# Sheet1.net
KiCad netlist of a schematic drawn in Altium Designer
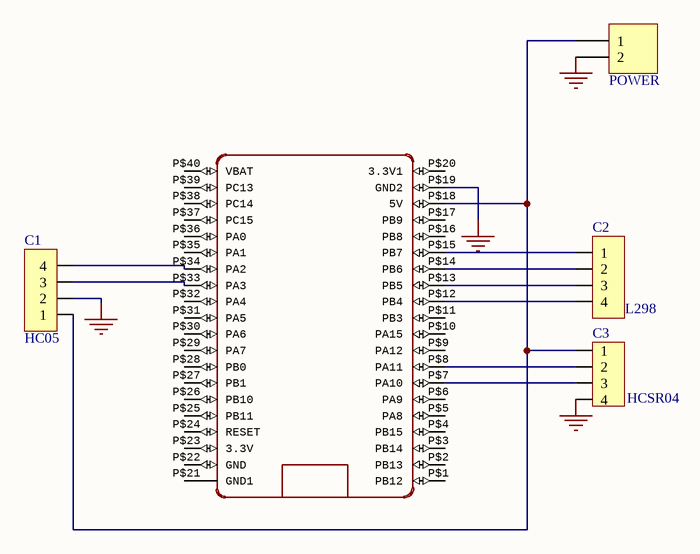
[diagram p0: Sheet1.SchDoc]

(export (version "E")
  (design (tool "Eeschema 10.0.6"))
  (components
    (comp (ref "C1")
      (value "HC05")
      (footprint "JP4-C1T")
      (description "WR-PHD 2.54 mm Angled Socket Header")
      (fields
        (field (name "MANUFACTURER") "Würth Elektronik eiSos GmbH")
        (field (name "PARTNO") "613004143121")
        (field (name "CREATED BY") "Karrer Zheng")
      )
      (libsource (lib "") (part "JP4_1"))
    )
    (comp (ref "C2")
      (value "L298")
      (footprint "JP4-C1T")
      (description "WR-PHD 2.54 mm Angled Socket Header")
      (fields
        (field (name "MANUFACTURER") "Würth Elektronik eiSos GmbH")
        (field (name "PARTNO") "613004143121")
        (field (name "CREATED BY") "Karrer Zheng")
      )
      (libsource (lib "LIBRARYALT") (part "JP4"))
    )
    (comp (ref "C3")
      (value "HCSR04")
      (footprint "Header4")
      (description "Header IDC, 4 x 1 Pin Vertical 2.54mm Pitch (Non-Boxed, Male)")
      (fields
        (field (name "MANUFACTURER") "Würth Elektronik eiSos GmbH")
        (field (name "PARTNO") "613002143121")
        (field (name "CREATED BY") "Karrer Zheng")
      )
      (libsource (lib "LIBRARYALT") (part "Header4"))
    )
    (comp (ref "POWER")
      (value "Header 2_1")
      (footprint "HED2")
      (description "Header, 2-Pin")
      (fields (field (name "MANUFACTURER") "Generic Components"))
      (libsource (lib "echipkool-com-library") (part "Header 2_1"))
    )
    (comp (ref "U")
      (value "BLUE_PILL")
      (footprint "BLUE_PILL")
      (libsource (lib "BluePill") (part "BLUE_PILL"))
    )
  )
  (nets
    (net (code "1") (name "GND") (class "Default")
      (node (ref "C1") (pin "2") (pinfunction "2_2") (pintype "passive"))
      (node (ref "C3") (pin "4") (pinfunction "4_4") (pintype "passive"))
      (node (ref "POWER") (pin "2") (pinfunction "2_2") (pintype "passive"))
      (node (ref "U") (pin "P$19") (pinfunction "GND2_P$19") (pintype "bidirectional"))
    )
    (net (code "2") (name "Net-(U-5V)") (class "Default")
      (node (ref "C1") (pin "1") (pinfunction "1_1") (pintype "passive"))
      (node (ref "C3") (pin "1") (pinfunction "1_1") (pintype "passive"))
      (node (ref "POWER") (pin "1") (pinfunction "1_1") (pintype "passive"))
      (node (ref "U") (pin "P$18") (pinfunction "5V_P$18") (pintype "bidirectional"))
    )
    (net (code "3") (name "Net-(U-PA2)") (class "Default")
      (node (ref "C1") (pin "4") (pinfunction "4_4") (pintype "passive"))
      (node (ref "U") (pin "P$34") (pinfunction "PA2_P$34") (pintype "bidirectional"))
    )
    (net (code "4") (name "Net-(U-PA3)") (class "Default")
      (node (ref "C1") (pin "3") (pinfunction "3_3") (pintype "passive"))
      (node (ref "U") (pin "P$33") (pinfunction "PA3_P$33") (pintype "bidirectional"))
    )
    (net (code "5") (name "Net-(U-PA10)") (class "Default")
      (node (ref "C3") (pin "3") (pinfunction "3_3") (pintype "passive"))
      (node (ref "U") (pin "P$7") (pinfunction "PA10_P$7") (pintype "bidirectional"))
    )
    (net (code "6") (name "Net-(U-PA11)") (class "Default")
      (node (ref "C3") (pin "2") (pinfunction "2_2") (pintype "passive"))
      (node (ref "U") (pin "P$8") (pinfunction "PA11_P$8") (pintype "bidirectional"))
    )
    (net (code "7") (name "Net-(U-PB4)") (class "Default")
      (node (ref "C2") (pin "4") (pinfunction "4_4") (pintype "passive"))
      (node (ref "U") (pin "P$12") (pinfunction "PB4_P$12") (pintype "bidirectional"))
    )
    (net (code "8") (name "Net-(U-PB5)") (class "Default")
      (node (ref "C2") (pin "3") (pinfunction "3_3") (pintype "passive"))
      (node (ref "U") (pin "P$13") (pinfunction "PB5_P$13") (pintype "bidirectional"))
    )
    (net (code "9") (name "Net-(U-PB6)") (class "Default")
      (node (ref "C2") (pin "2") (pinfunction "2_2") (pintype "passive"))
      (node (ref "U") (pin "P$14") (pinfunction "PB6_P$14") (pintype "bidirectional"))
    )
    (net (code "10") (name "Net-(U-PB7)") (class "Default")
      (node (ref "C2") (pin "1") (pinfunction "1_1") (pintype "passive"))
      (node (ref "U") (pin "P$15") (pinfunction "PB7_P$15") (pintype "bidirectional"))
    )
    (net (code "11") (name "unconnected-(U-3.3V-PadP$23)") (class "Default")
      (node (ref "U") (pin "P$23") (pinfunction "3.3V_P$23") (pintype "bidirectional"))
    )
    (net (code "12") (name "unconnected-(U-3.3V1-PadP$20)") (class "Default")
      (node (ref "U") (pin "P$20") (pinfunction "3.3V1_P$20") (pintype "bidirectional"))
    )
    (net (code "13") (name "unconnected-(U-GND-PadP$22)") (class "Default")
      (node (ref "U") (pin "P$22") (pinfunction "GND_P$22") (pintype "bidirectional"))
    )
    (net (code "14") (name "unconnected-(U-GND1-PadP$21)") (class "Default")
      (node (ref "U") (pin "P$21") (pinfunction "GND1_P$21") (pintype "power_in"))
    )
    (net (code "15") (name "unconnected-(U-PA0-PadP$36)") (class "Default")
      (node (ref "U") (pin "P$36") (pinfunction "PA0_P$36") (pintype "bidirectional"))
    )
    (net (code "16") (name "unconnected-(U-PA1-PadP$35)") (class "Default")
      (node (ref "U") (pin "P$35") (pinfunction "PA1_P$35") (pintype "bidirectional"))
    )
    (net (code "17") (name "unconnected-(U-PA4-PadP$32)") (class "Default")
      (node (ref "U") (pin "P$32") (pinfunction "PA4_P$32") (pintype "bidirectional"))
    )
    (net (code "18") (name "unconnected-(U-PA5-PadP$31)") (class "Default")
      (node (ref "U") (pin "P$31") (pinfunction "PA5_P$31") (pintype "bidirectional"))
    )
    (net (code "19") (name "unconnected-(U-PA6-PadP$30)") (class "Default")
      (node (ref "U") (pin "P$30") (pinfunction "PA6_P$30") (pintype "bidirectional"))
    )
    (net (code "20") (name "unconnected-(U-PA7-PadP$29)") (class "Default")
      (node (ref "U") (pin "P$29") (pinfunction "PA7_P$29") (pintype "bidirectional"))
    )
    (net (code "21") (name "unconnected-(U-PA8-PadP$5)") (class "Default")
      (node (ref "U") (pin "P$5") (pinfunction "PA8_P$5") (pintype "bidirectional"))
    )
    (net (code "22") (name "unconnected-(U-PA9-PadP$6)") (class "Default")
      (node (ref "U") (pin "P$6") (pinfunction "PA9_P$6") (pintype "bidirectional"))
    )
    (net (code "23") (name "unconnected-(U-PA12-PadP$9)") (class "Default")
      (node (ref "U") (pin "P$9") (pinfunction "PA12_P$9") (pintype "bidirectional"))
    )
    (net (code "24") (name "unconnected-(U-PA15-PadP$10)") (class "Default")
      (node (ref "U") (pin "P$10") (pinfunction "PA15_P$10") (pintype "bidirectional"))
    )
    (net (code "25") (name "unconnected-(U-PB0-PadP$28)") (class "Default")
      (node (ref "U") (pin "P$28") (pinfunction "PB0_P$28") (pintype "bidirectional"))
    )
    (net (code "26") (name "unconnected-(U-PB1-PadP$27)") (class "Default")
      (node (ref "U") (pin "P$27") (pinfunction "PB1_P$27") (pintype "bidirectional"))
    )
    (net (code "27") (name "unconnected-(U-PB3-PadP$11)") (class "Default")
      (node (ref "U") (pin "P$11") (pinfunction "PB3_P$11") (pintype "bidirectional"))
    )
    (net (code "28") (name "unconnected-(U-PB8-PadP$16)") (class "Default")
      (node (ref "U") (pin "P$16") (pinfunction "PB8_P$16") (pintype "bidirectional"))
    )
    (net (code "29") (name "unconnected-(U-PB9-PadP$17)") (class "Default")
      (node (ref "U") (pin "P$17") (pinfunction "PB9_P$17") (pintype "bidirectional"))
    )
    (net (code "30") (name "unconnected-(U-PB10-PadP$26)") (class "Default")
      (node (ref "U") (pin "P$26") (pinfunction "PB10_P$26") (pintype "bidirectional"))
    )
    (net (code "31") (name "unconnected-(U-PB11-PadP$25)") (class "Default")
      (node (ref "U") (pin "P$25") (pinfunction "PB11_P$25") (pintype "bidirectional"))
    )
    (net (code "32") (name "unconnected-(U-PB12-PadP$1)") (class "Default")
      (node (ref "U") (pin "P$1") (pinfunction "PB12_P$1") (pintype "bidirectional"))
    )
    (net (code "33") (name "unconnected-(U-PB13-PadP$2)") (class "Default")
      (node (ref "U") (pin "P$2") (pinfunction "PB13_P$2") (pintype "bidirectional"))
    )
    (net (code "34") (name "unconnected-(U-PB14-PadP$3)") (class "Default")
      (node (ref "U") (pin "P$3") (pinfunction "PB14_P$3") (pintype "bidirectional"))
    )
    (net (code "35") (name "unconnected-(U-PB15-PadP$4)") (class "Default")
      (node (ref "U") (pin "P$4") (pinfunction "PB15_P$4") (pintype "bidirectional"))
    )
    (net (code "36") (name "unconnected-(U-PC13-PadP$39)") (class "Default")
      (node (ref "U") (pin "P$39") (pinfunction "PC13_P$39") (pintype "bidirectional"))
    )
    (net (code "37") (name "unconnected-(U-PC14-PadP$38)") (class "Default")
      (node (ref "U") (pin "P$38") (pinfunction "PC14_P$38") (pintype "bidirectional"))
    )
    (net (code "38") (name "unconnected-(U-PC15-PadP$37)") (class "Default")
      (node (ref "U") (pin "P$37") (pinfunction "PC15_P$37") (pintype "bidirectional"))
    )
    (net (code "39") (name "unconnected-(U-RESET-PadP$24)") (class "Default")
      (node (ref "U") (pin "P$24") (pinfunction "RESET_P$24") (pintype "bidirectional"))
    )
    (net (code "40") (name "unconnected-(U-VBAT-PadP$40)") (class "Default")
      (node (ref "U") (pin "P$40") (pinfunction "VBAT_P$40") (pintype "bidirectional"))
    )
  )
)
